# LCD4_3.net
KiCad netlist of a schematic drawn in Altium Designer
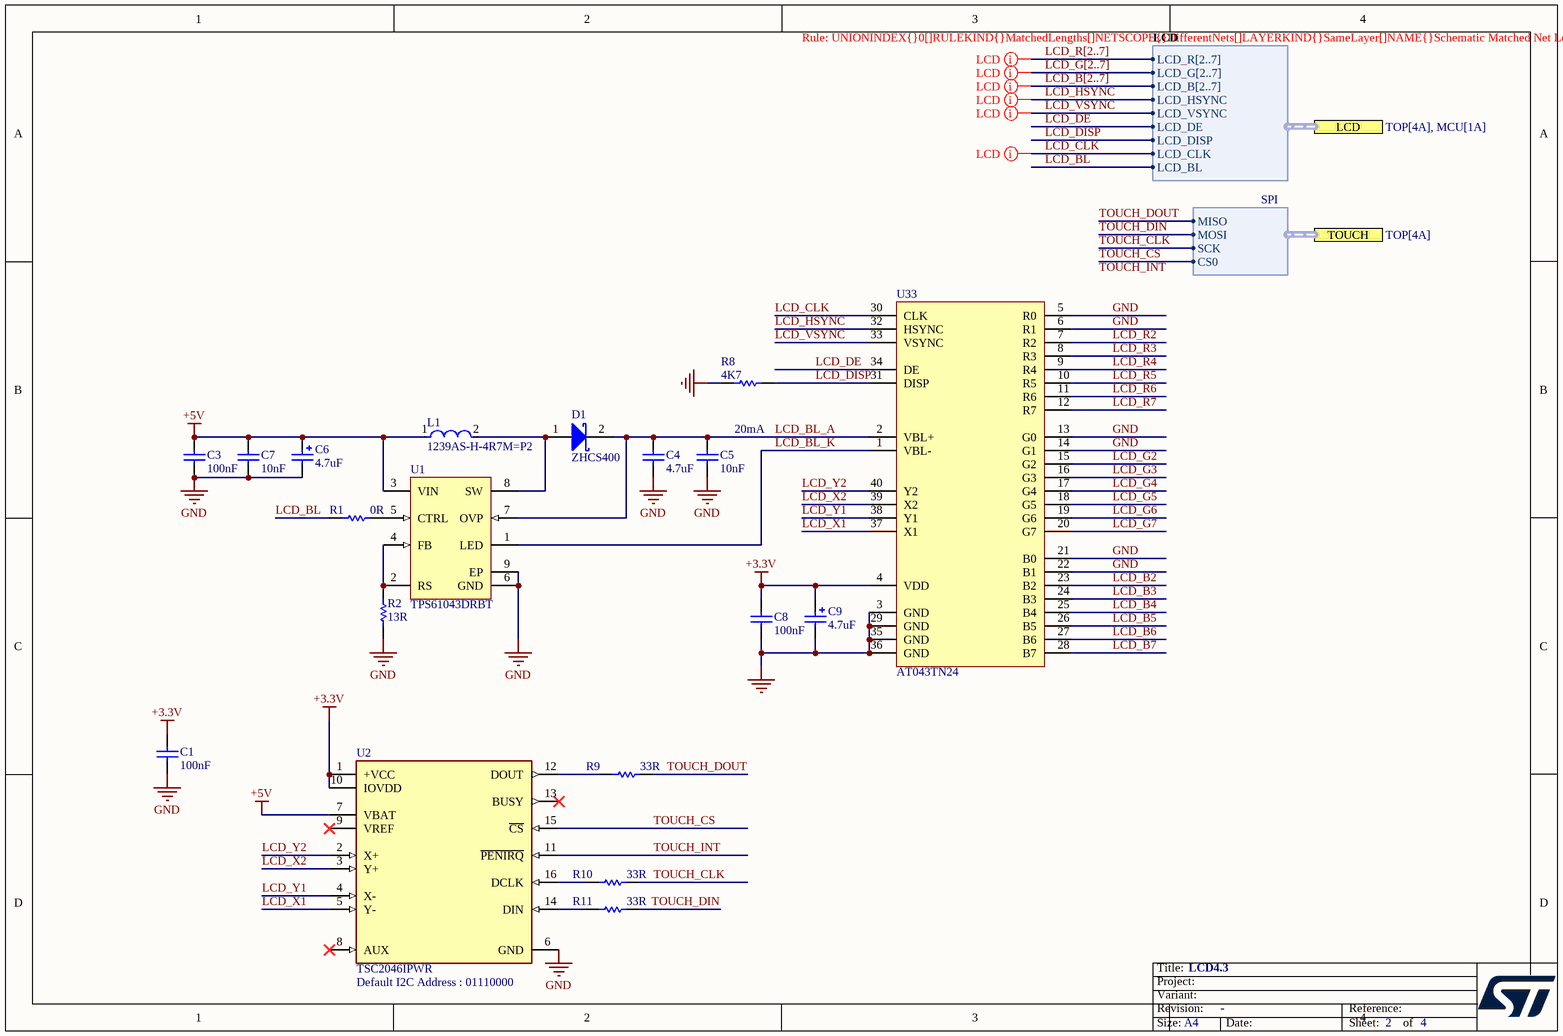
[diagram p0: LCD4.3.SchDoc]

(export (version "E")
  (design (tool "Eeschema 10.0.6"))
  (components
    (comp (ref "C1")
      (value "100nF")
      (footprint "C603")
      (description "Capacitor, MLCC, 100nF, 16V, X7R, 10%, 0402, T=0,5mm")
      (fields
        (field (name "INTERNAL_PART_NUMBER") "MCD-00102")
        (field (name "MANUFACTURER_PART_NUMBER") "CC0402KRX7R7BB104")
        (field (name "PROVIDED_BY") "Subcon")
      )
      (libsource (lib "MCD_PARTS_database") (part "Capacitor"))
    )
    (comp (ref "C3")
      (value "100nF")
      (footprint "C603")
      (description "Capacitor, MLCC, 100nF, 16V, X7R, 10%, 0402, T=0,5mm")
      (fields
        (field (name "INTERNAL_PART_NUMBER") "MCD-00102")
        (field (name "MANUFACTURER_PART_NUMBER") "CC0402KRX7R7BB104")
        (field (name "PROVIDED_BY") "Subcon")
      )
      (libsource (lib "MCD_PARTS_database") (part "Capacitor"))
    )
    (comp (ref "C4")
      (value "4.7uF")
      (footprint "C1206")
      (description "Capacitor, MLCC, 4.7uF, 50V, X7R, 10%, 1206, T=1,27mm")
      (fields
        (field (name "INTERNAL_PART_NUMBER") "MCD-00013")
        (field (name "MANUFACTURER_PART_NUMBER") "12065C475KAT2A")
        (field (name "PROVIDED_BY") "Subcon")
      )
      (libsource (lib "MCD_PARTS_database") (part "Capacitor"))
    )
    (comp (ref "C5")
      (value "10nF")
      (footprint "C603")
      (description "Capacitor, MLCC, 10nF, 50V, X7R, 10%, 0603, T=0.8mm")
      (fields
        (field (name "INTERNAL_PART_NUMBER") "MCD-00017")
        (field (name "MANUFACTURER_PART_NUMBER") "CC0603KRX7R9BB103")
        (field (name "PROVIDED_BY") "Subcon")
      )
      (libsource (lib "MCD_PARTS_database") (part "Capacitor"))
    )
    (comp (ref "C6")
      (value "4.7uF")
      (footprint "CAP-TAN-A")
      (description "Capacitor, Tantalum, 4.7uF, 16V, +/-10%, 595D case A")
      (fields
        (field (name "INTERNAL_PART_NUMBER") "MCD-00595")
        (field (name "MANUFACTURER_PART_NUMBER") "595D475X9016A2T")
        (field (name "PROVIDED_BY") "Subcon")
      )
      (libsource (lib "MCD_PARTS_database") (part "Cap_POL_TANA"))
    )
    (comp (ref "C7")
      (value "10nF")
      (footprint "C603")
      (description "Capacitor, MLCC, 10nF, 50V, X7R, 10%, 0603, T=0.8mm")
      (fields
        (field (name "INTERNAL_PART_NUMBER") "MCD-00017")
        (field (name "MANUFACTURER_PART_NUMBER") "CC0603KRX7R9BB103")
        (field (name "PROVIDED_BY") "Subcon")
      )
      (libsource (lib "MCD_PARTS_database") (part "Capacitor"))
    )
    (comp (ref "C8")
      (value "100nF")
      (footprint "C603")
      (description "Capacitor, MLCC, 100nF, 16V, X7R, 10%, 0402, T=0,5mm")
      (fields
        (field (name "INTERNAL_PART_NUMBER") "MCD-00102")
        (field (name "MANUFACTURER_PART_NUMBER") "CC0402KRX7R7BB104")
        (field (name "PROVIDED_BY") "Subcon")
      )
      (libsource (lib "MCD_PARTS_database") (part "Capacitor"))
    )
    (comp (ref "C9")
      (value "4.7uF")
      (footprint "CAP-TAN-A")
      (description "Capacitor, Tantalum, 4.7uF, 16V, +/-10%, 595D case A")
      (fields
        (field (name "INTERNAL_PART_NUMBER") "MCD-00595")
        (field (name "MANUFACTURER_PART_NUMBER") "595D475X9016A2T")
        (field (name "PROVIDED_BY") "Subcon")
      )
      (libsource (lib "MCD_PARTS_database") (part "Cap_POL_TANA"))
    )
    (comp (ref "D1")
      (value "ZHCS400")
      (footprint "DIOD-SOD323-2_V")
      (description "Schottky Diode, 400mA")
      (fields (field (name "MANUFACTURER") "Diodes Inc"))
      (libsource (lib "Altium Content Vault") (part "DIOD-DSKY-A1K2-2"))
    )
    (comp (ref "L1")
      (value "1239AS-H-4R7M=P2")
      (footprint "FP-DFE252012C-IPC_A")
      (description "Shielded Wirewound Inductor 4.7uH 20% 1300mA 0.24Ω 1008 (2520)")
      (fields (field (name "TOLERANCE") "20%"))
      (libsource (lib "Altium Content Vault") (part "725321dda6339637d4d059423bc1c3c"))
    )
    (comp (ref "R1")
      (value "0R")
      (footprint "R0603")
      (description "Resistor,0R,0603,ULO")
      (fields
        (field (name "INTERNAL_PART_NUMBER") "MCD-00181")
        (field (name "MANUFACTURER_PART_NUMBER") "PMR03EZPJ000")
        (field (name "PROVIDED_BY") "Subcon")
      )
      (libsource (lib "MCD_PARTS_database") (part "Resistor"))
    )
    (comp (ref "R2")
      (value "13R")
      (footprint "R805")
      (description "Resistor,10R,0805,1%,Stackpole,1/4W")
      (fields
        (field (name "INTERNAL_PART_NUMBER") "MCD-01111")
        (field (name "MANUFACTURER_PART_NUMBER") "RNCP0805FTD10R0")
        (field (name "PROVIDED_BY") "Subcon")
      )
      (libsource (lib "MCD_PARTS_database") (part "Resistor"))
    )
    (comp (ref "R8")
      (value "4K7")
      (footprint "R0603")
      (description "Resistor,4K7,0603,1%,1/10W")
      (fields
        (field (name "INTERNAL_PART_NUMBER") "MCD-00219")
        (field (name "MANUFACTURER_PART_NUMBER") "RC0603FR-074K7L")
        (field (name "PROVIDED_BY") "Subcon")
      )
      (libsource (lib "MCD_PARTS_database") (part "Resistor"))
    )
    (comp (ref "R9")
      (value "33R")
      (footprint "R0603")
      (description "Resistor,33R,0402,1%,1/16W")
      (fields
        (field (name "INTERNAL_PART_NUMBER") "MCD-00455")
        (field (name "MANUFACTURER_PART_NUMBER") "RC0402FR-0733RL")
        (field (name "PROVIDED_BY") "Subcon")
      )
      (libsource (lib "MCD_PARTS_database") (part "Resistor"))
    )
    (comp (ref "R10")
      (value "33R")
      (footprint "R0603")
      (description "Resistor,33R,0402,1%,1/16W")
      (fields
        (field (name "INTERNAL_PART_NUMBER") "MCD-00455")
        (field (name "MANUFACTURER_PART_NUMBER") "RC0402FR-0733RL")
        (field (name "PROVIDED_BY") "Subcon")
      )
      (libsource (lib "MCD_PARTS_database") (part "Resistor"))
    )
    (comp (ref "R11")
      (value "33R")
      (footprint "R0603")
      (description "Resistor,33R,0402,1%,1/16W")
      (fields
        (field (name "INTERNAL_PART_NUMBER") "MCD-00455")
        (field (name "MANUFACTURER_PART_NUMBER") "RC0402FR-0733RL")
        (field (name "PROVIDED_BY") "Subcon")
      )
      (libsource (lib "MCD_PARTS_database") (part "Resistor"))
    )
    (comp (ref "U1")
      (value "TPS61043DRBT")
      (footprint "DRB0008A_V")
      (fields (field (name "MANUFACTURER") "Texas Instruments"))
      (libsource (lib "Altium Content Vault") (part "TI-TPS61043DRB8-1750X1500TP"))
    )
    (comp (ref "U2")
      (value "TSC2046IPWR")
      (footprint "FP-PW0016A-IPC_B")
      (description "IC SCREEN CNTRL 12BIT 16TSSOP")
      (libsource (lib "Altium Content Vault") (part "1671dc8fda4feff936ea170ccf132c6"))
    )
    (comp (ref "U33")
      (value "AT043TN24")
      (footprint "FPC-40")
      (fields
        (field (name "INTERNAL_PART_NUMBER") "MCD-02422")
        (field (name "MANUFACTURER") "ROCKTECH")
        (field (name "MANUFACTURER_PART_NUMBER") "RK043FN78HV-CT661C")
      )
      (libsource (lib "Schlib1") (part "AT043TN24"))
    )
  )
  (nets
    (net (code "3") (name "+3.3V") (class "Default")
      (node (ref "C1") (pin "2") (pinfunction "2_2") (pintype "passive"))
      (node (ref "C8") (pin "2") (pinfunction "2_2") (pintype "passive"))
      (node (ref "C9") (pin "1") (pinfunction "1_1") (pintype "passive"))
      (node (ref "U2") (pin "1") (pinfunction "+VCC_1") (pintype "power_in"))
      (node (ref "U2") (pin "10") (pinfunction "IOVDD_10") (pintype "power_in"))
      (node (ref "U33") (pin "4") (pinfunction "VDD_4") (pintype "passive"))
    )
    (net (code "4") (name "+5V") (class "Default")
      (node (ref "C3") (pin "2") (pinfunction "2_2") (pintype "passive"))
      (node (ref "C6") (pin "1") (pinfunction "1_1") (pintype "passive"))
      (node (ref "C7") (pin "2") (pinfunction "2_2") (pintype "passive"))
      (node (ref "L1") (pin "1") (pinfunction "1_1") (pintype "passive"))
      (node (ref "U1") (pin "3") (pinfunction "VIN_3") (pintype "power_in"))
      (node (ref "U2") (pin "7") (pinfunction "VBAT_7") (pintype "power_in"))
    )
    (net (code "5") (name "/LCD_B2") (class "Default")
      (node (ref "U33") (pin "23") (pinfunction "B2_23") (pintype "passive"))
    )
    (net (code "6") (name "/LCD_B3") (class "Default")
      (node (ref "U33") (pin "24") (pinfunction "B3_24") (pintype "passive"))
    )
    (net (code "7") (name "/LCD_B4") (class "Default")
      (node (ref "U33") (pin "25") (pinfunction "B4_25") (pintype "passive"))
    )
    (net (code "8") (name "/LCD_B5") (class "Default")
      (node (ref "U33") (pin "26") (pinfunction "B5_26") (pintype "passive"))
    )
    (net (code "9") (name "/LCD_B6") (class "Default")
      (node (ref "U33") (pin "27") (pinfunction "B6_27") (pintype "passive"))
    )
    (net (code "10") (name "/LCD_B7") (class "Default")
      (node (ref "U33") (pin "28") (pinfunction "B7_28") (pintype "passive"))
    )
    (net (code "11") (name "/LCD_BL") (class "Default")
      (node (ref "R1") (pin "1") (pinfunction "1_1") (pintype "passive"))
    )
    (net (code "12") (name "/LCD_BL_A") (class "Default")
      (node (ref "C4") (pin "2") (pinfunction "2_2") (pintype "passive"))
      (node (ref "C5") (pin "2") (pinfunction "2_2") (pintype "passive"))
      (node (ref "D1") (pin "2") (pinfunction "K_2") (pintype "passive"))
      (node (ref "U1") (pin "7") (pinfunction "OVP_7") (pintype "input"))
      (node (ref "U33") (pin "2") (pinfunction "VBL+_2") (pintype "passive"))
    )
    (net (code "13") (name "/LCD_BL_K") (class "Default")
      (node (ref "U1") (pin "1") (pinfunction "LED_1") (pintype "passive"))
      (node (ref "U33") (pin "1") (pinfunction "VBL-_1") (pintype "passive"))
    )
    (net (code "15") (name "/LCD_CLK") (class "Default")
      (node (ref "U33") (pin "30") (pinfunction "CLK_30") (pintype "passive"))
    )
    (net (code "16") (name "/LCD_DE") (class "Default")
      (node (ref "U33") (pin "34") (pinfunction "DE_34") (pintype "passive"))
    )
    (net (code "17") (name "/LCD_DISP") (class "Default")
      (node (ref "R8") (pin "2") (pinfunction "2_2") (pintype "passive"))
      (node (ref "U33") (pin "31") (pinfunction "DISP_31") (pintype "passive"))
    )
    (net (code "18") (name "/LCD_G2") (class "Default")
      (node (ref "U33") (pin "15") (pinfunction "G2_15") (pintype "passive"))
    )
    (net (code "19") (name "/LCD_G3") (class "Default")
      (node (ref "U33") (pin "16") (pinfunction "G3_16") (pintype "passive"))
    )
    (net (code "20") (name "/LCD_G4") (class "Default")
      (node (ref "U33") (pin "17") (pinfunction "G4_17") (pintype "passive"))
    )
    (net (code "21") (name "/LCD_G5") (class "Default")
      (node (ref "U33") (pin "18") (pinfunction "G5_18") (pintype "passive"))
    )
    (net (code "22") (name "/LCD_G6") (class "Default")
      (node (ref "U33") (pin "19") (pinfunction "G6_19") (pintype "passive"))
    )
    (net (code "23") (name "/LCD_G7") (class "Default")
      (node (ref "U33") (pin "20") (pinfunction "G7_20") (pintype "passive"))
    )
    (net (code "25") (name "/LCD_HSYNC") (class "Default")
      (node (ref "U33") (pin "32") (pinfunction "HSYNC_32") (pintype "passive"))
    )
    (net (code "26") (name "/LCD_R2") (class "Default")
      (node (ref "U33") (pin "7") (pinfunction "R2_7") (pintype "passive"))
    )
    (net (code "27") (name "/LCD_R3") (class "Default")
      (node (ref "U33") (pin "8") (pinfunction "R3_8") (pintype "passive"))
    )
    (net (code "28") (name "/LCD_R4") (class "Default")
      (node (ref "U33") (pin "9") (pinfunction "R4_9") (pintype "passive"))
    )
    (net (code "29") (name "/LCD_R5") (class "Default")
      (node (ref "U33") (pin "10") (pinfunction "R5_10") (pintype "passive"))
    )
    (net (code "30") (name "/LCD_R6") (class "Default")
      (node (ref "U33") (pin "11") (pinfunction "R6_11") (pintype "passive"))
    )
    (net (code "31") (name "/LCD_R7") (class "Default")
      (node (ref "U33") (pin "12") (pinfunction "R7_12") (pintype "passive"))
    )
    (net (code "33") (name "/LCD_VSYNC") (class "Default")
      (node (ref "U33") (pin "33") (pinfunction "VSYNC_33") (pintype "passive"))
    )
    (net (code "34") (name "/LCD_X1") (class "Default")
      (node (ref "U2") (pin "5") (pinfunction "Y-_5") (pintype "input"))
      (node (ref "U33") (pin "37") (pinfunction "X1_37") (pintype "passive"))
    )
    (net (code "35") (name "/LCD_X2") (class "Default")
      (node (ref "U2") (pin "3") (pinfunction "Y+_3") (pintype "input"))
      (node (ref "U33") (pin "39") (pinfunction "X2_39") (pintype "passive"))
    )
    (net (code "36") (name "/LCD_Y1") (class "Default")
      (node (ref "U2") (pin "4") (pinfunction "X-_4") (pintype "input"))
      (node (ref "U33") (pin "38") (pinfunction "Y1_38") (pintype "passive"))
    )
    (net (code "37") (name "/LCD_Y2") (class "Default")
      (node (ref "U2") (pin "2") (pinfunction "X+_2") (pintype "input"))
      (node (ref "U33") (pin "40") (pinfunction "Y2_40") (pintype "passive"))
    )
    (net (code "38") (name "/TOUCH_CLK") (class "Default")
      (node (ref "R10") (pin "2") (pinfunction "2_2") (pintype "passive"))
    )
    (net (code "39") (name "/TOUCH_CS") (class "Default")
      (node (ref "U2") (pin "15") (pinfunction "~{CS}_15") (pintype "input"))
    )
    (net (code "40") (name "/TOUCH_DIN") (class "Default")
      (node (ref "R11") (pin "2") (pinfunction "2_2") (pintype "passive"))
    )
    (net (code "41") (name "/TOUCH_DOUT") (class "Default")
      (node (ref "R9") (pin "2") (pinfunction "2_2") (pintype "passive"))
    )
    (net (code "42") (name "/TOUCH_INT") (class "Default")
      (node (ref "U2") (pin "11") (pinfunction "~{PENIRQ}_11") (pintype "input"))
    )
    (net (code "45") (name "GND") (class "Default")
      (node (ref "C1") (pin "1") (pinfunction "1_1") (pintype "passive"))
      (node (ref "C3") (pin "1") (pinfunction "1_1") (pintype "passive"))
      (node (ref "C4") (pin "1") (pinfunction "1_1") (pintype "passive"))
      (node (ref "C5") (pin "1") (pinfunction "1_1") (pintype "passive"))
      (node (ref "C6") (pin "2") (pinfunction "2_2") (pintype "passive"))
      (node (ref "C7") (pin "1") (pinfunction "1_1") (pintype "passive"))
      (node (ref "C8") (pin "1") (pinfunction "1_1") (pintype "passive"))
      (node (ref "C9") (pin "2") (pinfunction "2_2") (pintype "passive"))
      (node (ref "R2") (pin "1") (pinfunction "1_1") (pintype "passive"))
      (node (ref "R8") (pin "1") (pinfunction "1_1") (pintype "passive"))
      (node (ref "U1") (pin "6") (pinfunction "GND_6") (pintype "power_in"))
      (node (ref "U1") (pin "9") (pinfunction "EP_9") (pintype "power_in"))
      (node (ref "U2") (pin "6") (pinfunction "GND_6") (pintype "power_in"))
      (node (ref "U33") (pin "13") (pinfunction "G0_13") (pintype "passive"))
      (node (ref "U33") (pin "14") (pinfunction "G1_14") (pintype "passive"))
      (node (ref "U33") (pin "21") (pinfunction "B0_21") (pintype "passive"))
      (node (ref "U33") (pin "22") (pinfunction "B1_22") (pintype "passive"))
      (node (ref "U33") (pin "29") (pinfunction "GND_29") (pintype "passive"))
      (node (ref "U33") (pin "3") (pinfunction "GND_3") (pintype "passive"))
      (node (ref "U33") (pin "35") (pinfunction "GND_35") (pintype "passive"))
      (node (ref "U33") (pin "36") (pinfunction "GND_36") (pintype "passive"))
      (node (ref "U33") (pin "5") (pinfunction "R0_5") (pintype "passive"))
      (node (ref "U33") (pin "6") (pinfunction "R1_6") (pintype "passive"))
    )
    (net (code "46") (name "Net-(D1-A)") (class "Default")
      (node (ref "D1") (pin "1") (pinfunction "A_1") (pintype "passive"))
      (node (ref "L1") (pin "2") (pinfunction "2_2") (pintype "passive"))
      (node (ref "U1") (pin "8") (pinfunction "SW_8") (pintype "power_in"))
    )
    (net (code "47") (name "Net-(U1-CTRL)") (class "Default")
      (node (ref "R1") (pin "2") (pinfunction "2_2") (pintype "passive"))
      (node (ref "U1") (pin "5") (pinfunction "CTRL_5") (pintype "input"))
    )
    (net (code "48") (name "Net-(U1-FB)") (class "Default")
      (node (ref "R2") (pin "2") (pinfunction "2_2") (pintype "passive"))
      (node (ref "U1") (pin "2") (pinfunction "RS_2") (pintype "passive"))
      (node (ref "U1") (pin "4") (pinfunction "FB_4") (pintype "input"))
    )
    (net (code "49") (name "Net-(U2-DCLK)") (class "Default")
      (node (ref "R10") (pin "1") (pinfunction "1_1") (pintype "passive"))
      (node (ref "U2") (pin "16") (pinfunction "DCLK_16") (pintype "input"))
    )
    (net (code "50") (name "Net-(U2-DIN)") (class "Default")
      (node (ref "R11") (pin "1") (pinfunction "1_1") (pintype "passive"))
      (node (ref "U2") (pin "14") (pinfunction "DIN_14") (pintype "input"))
    )
    (net (code "51") (name "Net-(U2-DOUT)") (class "Default")
      (node (ref "R9") (pin "1") (pinfunction "1_1") (pintype "passive"))
      (node (ref "U2") (pin "12") (pinfunction "DOUT_12") (pintype "output"))
    )
    (net (code "52") (name "unconnected-(U2-AUX-Pad8)") (class "Default")
      (node (ref "U2") (pin "8") (pinfunction "AUX_8") (pintype "input+no_connect"))
    )
    (net (code "53") (name "unconnected-(U2-BUSY-Pad13)") (class "Default")
      (node (ref "U2") (pin "13") (pinfunction "BUSY_13") (pintype "output+no_connect"))
    )
    (net (code "54") (name "unconnected-(U2-VREF-Pad9)") (class "Default")
      (node (ref "U2") (pin "9") (pinfunction "VREF_9") (pintype "power_in+no_connect"))
    )
  )
)
